# Master.net
KiCad netlist of a schematic drawn in EAGLE
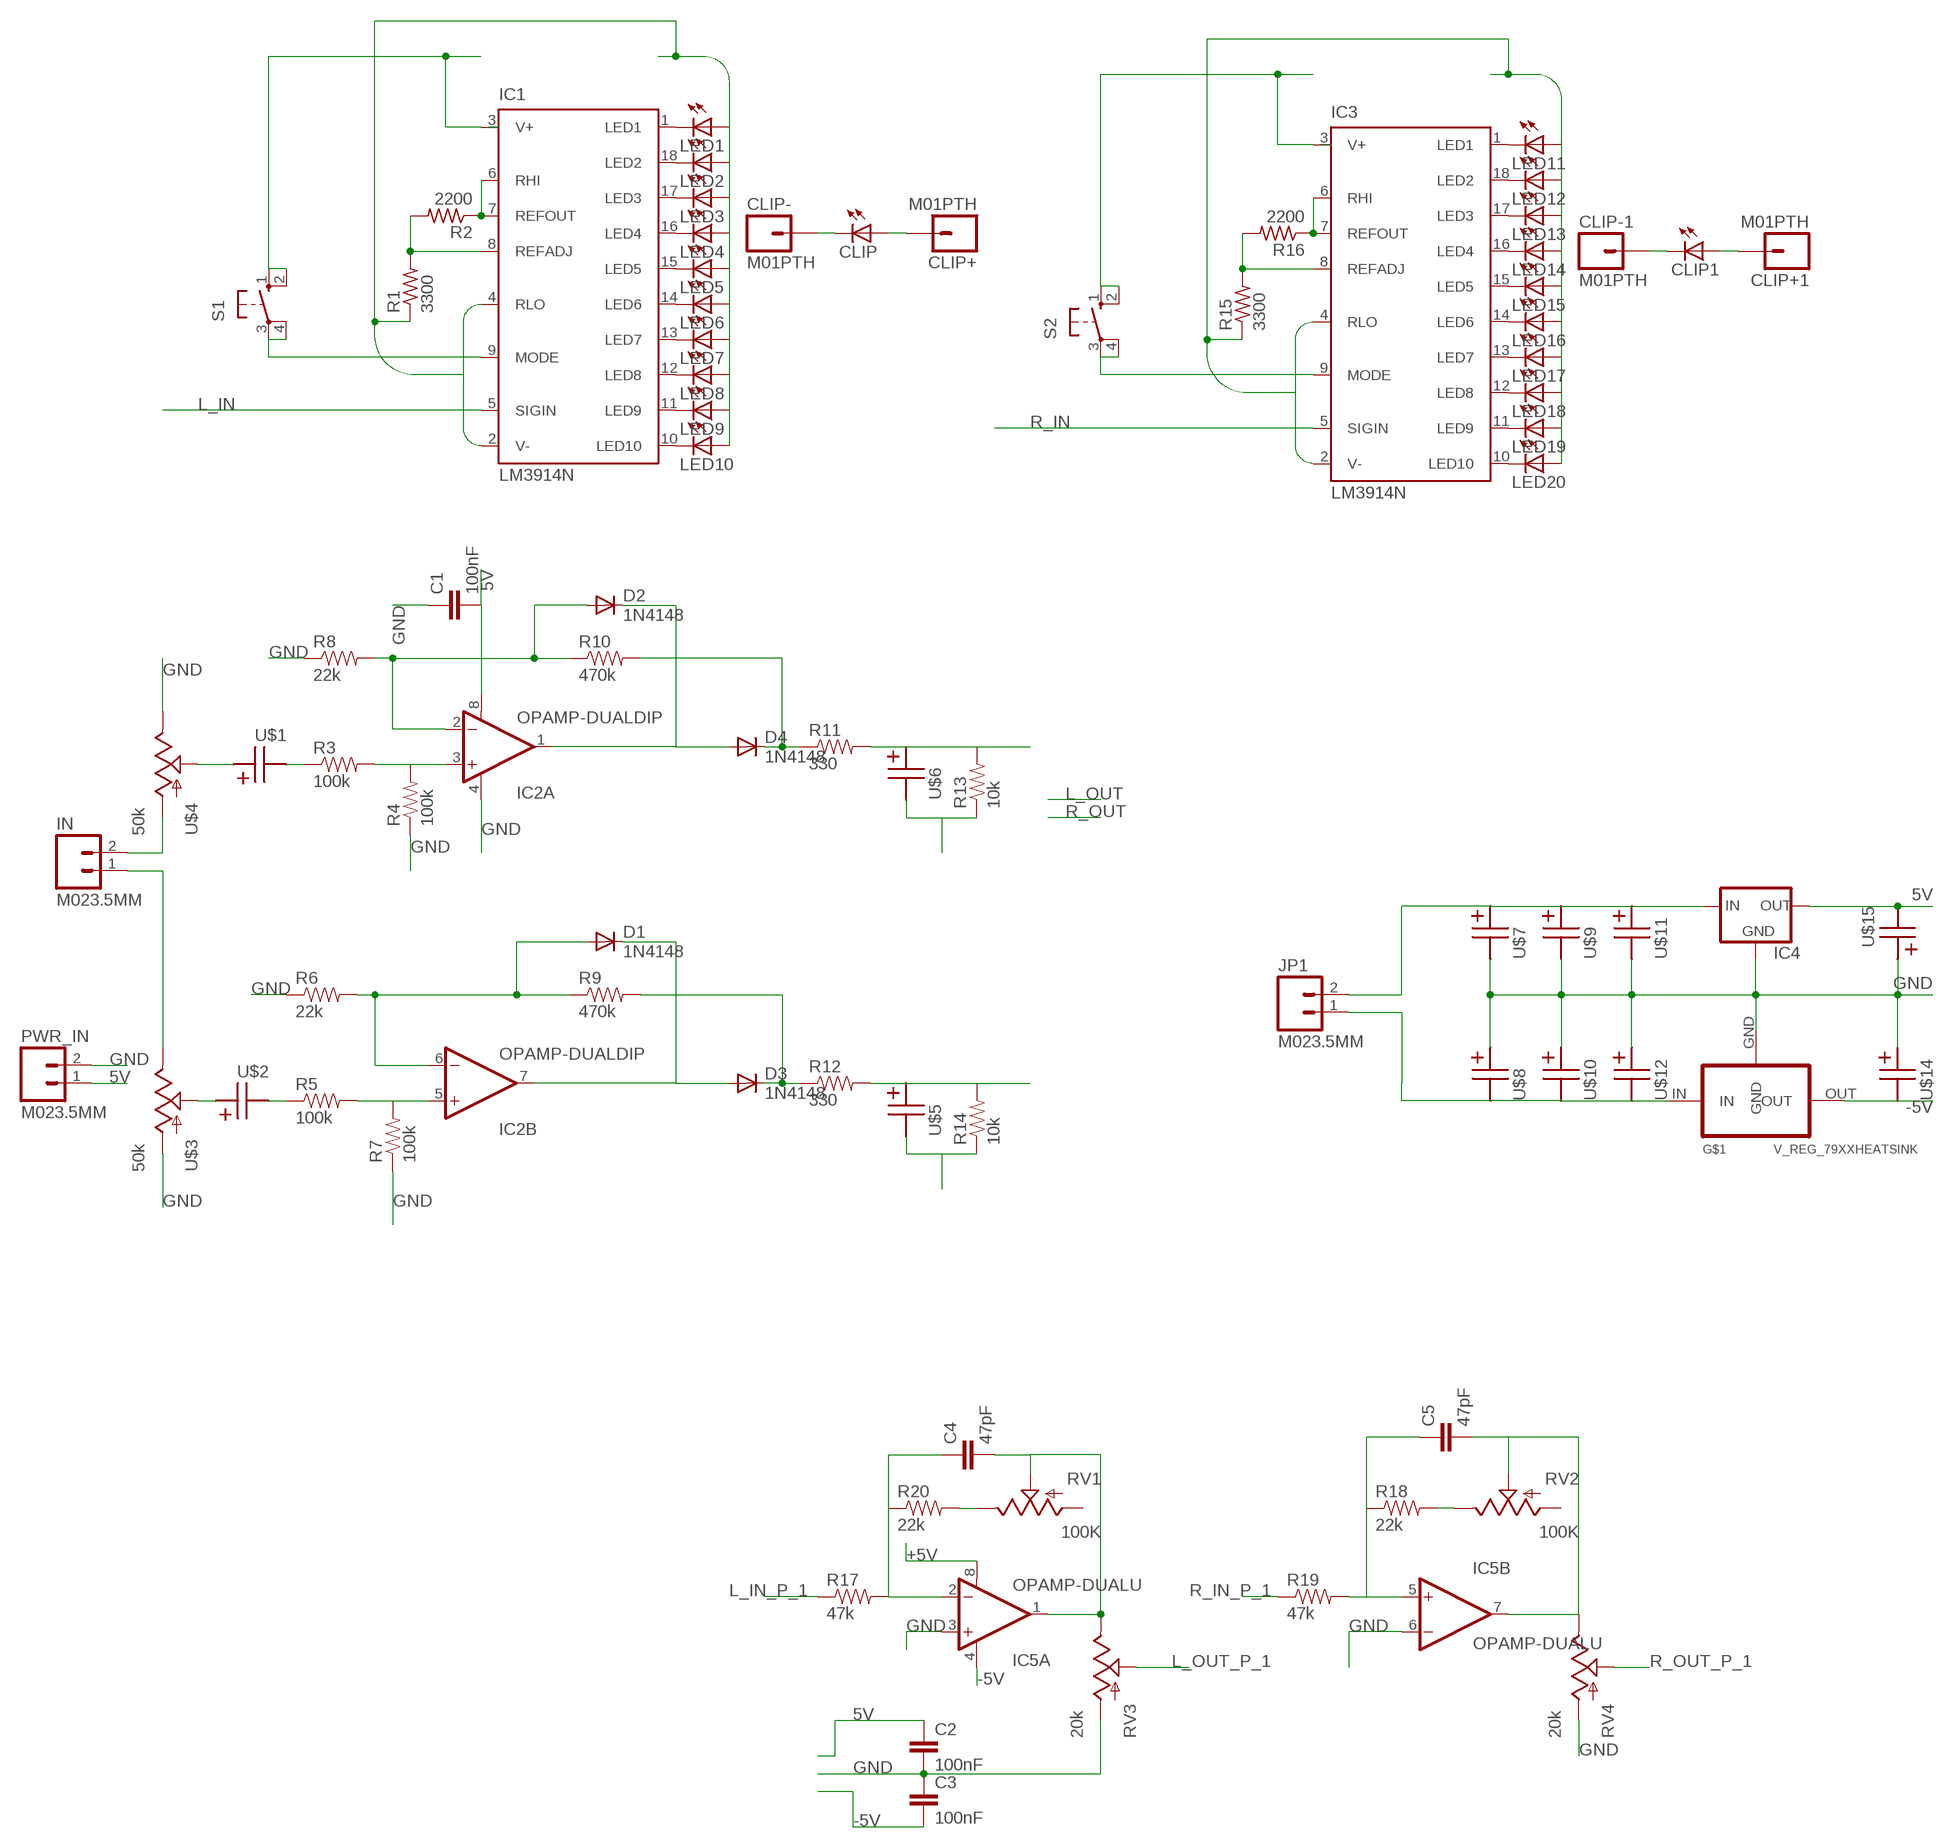
[diagram p0: schematic, sheet 1]

(export (version "E")
  (design (tool "Eeschema 10.0.6"))
  (components
    (comp (ref "C1")
      (value "100nF")
      (footprint "eagle-import:0805")
      (libsource (lib "eagle-import") (part "CAP0805"))
    )
    (comp (ref "C2")
      (value "100nF")
      (footprint "eagle-import:1206")
      (libsource (lib "eagle-import") (part "CAP1206"))
    )
    (comp (ref "C3")
      (value "100nF")
      (footprint "eagle-import:1206")
      (libsource (lib "eagle-import") (part "CAP1206"))
    )
    (comp (ref "C4")
      (value "47pF")
      (footprint "eagle-import:0805")
      (libsource (lib "eagle-import") (part "CAP0805"))
    )
    (comp (ref "C5")
      (value "47pF")
      (footprint "eagle-import:0805")
      (libsource (lib "eagle-import") (part "CAP0805"))
    )
    (comp (ref "CLIP")
      (value "LED5MM")
      (footprint "eagle-import:LED5MM")
      (libsource (lib "eagle-import") (part "LED5MM"))
    )
    (comp (ref "CLIP+")
      (value "M01PTH")
      (footprint "eagle-import:1X01")
      (libsource (lib "eagle-import") (part "M01PTH"))
    )
    (comp (ref "CLIP+1")
      (value "M01PTH")
      (footprint "eagle-import:1X01")
      (libsource (lib "eagle-import") (part "M01PTH"))
    )
    (comp (ref "CLIP-")
      (value "M01PTH")
      (footprint "eagle-import:1X01")
      (libsource (lib "eagle-import") (part "M01PTH"))
    )
    (comp (ref "CLIP-1")
      (value "M01PTH")
      (footprint "eagle-import:1X01")
      (libsource (lib "eagle-import") (part "M01PTH"))
    )
    (comp (ref "CLIP1")
      (value "LED5MM")
      (footprint "eagle-import:LED5MM")
      (libsource (lib "eagle-import") (part "LED5MM"))
    )
    (comp (ref "D1")
      (value "1N4148")
      (footprint "eagle-import:DIODE-1N4148")
      (libsource (lib "eagle-import") (part "DIODE1N4148"))
    )
    (comp (ref "D2")
      (value "1N4148")
      (footprint "eagle-import:DIODE-1N4148")
      (libsource (lib "eagle-import") (part "DIODE1N4148"))
    )
    (comp (ref "D3")
      (value "1N4148")
      (footprint "eagle-import:DIODE-1N4148")
      (libsource (lib "eagle-import") (part "DIODE1N4148"))
    )
    (comp (ref "D4")
      (value "1N4148")
      (footprint "eagle-import:DIODE-1N4148")
      (libsource (lib "eagle-import") (part "DIODE1N4148"))
    )
    (comp (ref "IC1")
      (value "LM3914N")
      (footprint "eagle-import:DIL18")
      (libsource (lib "eagle-import") (part "LM391N4"))
    )
    (comp (ref "IC2")
      (value "OPAMP-DUALDIP")
      (footprint "eagle-import:DIP08")
      (libsource (lib "eagle-import") (part "OPAMP-DUALDIP"))
    )
    (comp (ref "IC3")
      (value "LM3914N")
      (footprint "eagle-import:DIL18")
      (libsource (lib "eagle-import") (part "LM391N4"))
    )
    (comp (ref "IC4")
      (value "V_REG_78XXSINK")
      (footprint "eagle-import:TO220-IGO")
      (libsource (lib "eagle-import") (part "V_REG_78XXSINK"))
    )
    (comp (ref "IC5")
      (value "OPAMP-DUALU")
      (footprint "eagle-import:SO08")
      (libsource (lib "eagle-import") (part "OPAMP-DUALU"))
    )
    (comp (ref "IN")
      (value "M023.5MM")
      (footprint "eagle-import:SCREWTERMINAL-3.5MM-2")
      (libsource (lib "eagle-import") (part "M023.5MM"))
    )
    (comp (ref "JP1")
      (value "M023.5MM")
      (footprint "eagle-import:SCREWTERMINAL-3.5MM-2")
      (libsource (lib "eagle-import") (part "M023.5MM"))
    )
    (comp (ref "LED1")
      (value "LED5MM")
      (footprint "eagle-import:LED5MM")
      (libsource (lib "eagle-import") (part "LED5MM"))
    )
    (comp (ref "LED2")
      (value "LED5MM")
      (footprint "eagle-import:LED5MM")
      (libsource (lib "eagle-import") (part "LED5MM"))
    )
    (comp (ref "LED3")
      (value "LED5MM")
      (footprint "eagle-import:LED5MM")
      (libsource (lib "eagle-import") (part "LED5MM"))
    )
    (comp (ref "LED4")
      (value "LED5MM")
      (footprint "eagle-import:LED5MM")
      (libsource (lib "eagle-import") (part "LED5MM"))
    )
    (comp (ref "LED5")
      (value "LED5MM")
      (footprint "eagle-import:LED5MM")
      (libsource (lib "eagle-import") (part "LED5MM"))
    )
    (comp (ref "LED6")
      (value "LED5MM")
      (footprint "eagle-import:LED5MM")
      (libsource (lib "eagle-import") (part "LED5MM"))
    )
    (comp (ref "LED7")
      (value "LED5MM")
      (footprint "eagle-import:LED5MM")
      (libsource (lib "eagle-import") (part "LED5MM"))
    )
    (comp (ref "LED8")
      (value "LED5MM")
      (footprint "eagle-import:LED5MM")
      (libsource (lib "eagle-import") (part "LED5MM"))
    )
    (comp (ref "LED9")
      (value "LED5MM")
      (footprint "eagle-import:LED5MM")
      (libsource (lib "eagle-import") (part "LED5MM"))
    )
    (comp (ref "LED10")
      (value "LED5MM")
      (footprint "eagle-import:LED5MM")
      (libsource (lib "eagle-import") (part "LED5MM"))
    )
    (comp (ref "LED11")
      (value "LED5MM")
      (footprint "eagle-import:LED5MM")
      (libsource (lib "eagle-import") (part "LED5MM"))
    )
    (comp (ref "LED12")
      (value "LED5MM")
      (footprint "eagle-import:LED5MM")
      (libsource (lib "eagle-import") (part "LED5MM"))
    )
    (comp (ref "LED13")
      (value "LED5MM")
      (footprint "eagle-import:LED5MM")
      (libsource (lib "eagle-import") (part "LED5MM"))
    )
    (comp (ref "LED14")
      (value "LED5MM")
      (footprint "eagle-import:LED5MM")
      (libsource (lib "eagle-import") (part "LED5MM"))
    )
    (comp (ref "LED15")
      (value "LED5MM")
      (footprint "eagle-import:LED5MM")
      (libsource (lib "eagle-import") (part "LED5MM"))
    )
    (comp (ref "LED16")
      (value "LED5MM")
      (footprint "eagle-import:LED5MM")
      (libsource (lib "eagle-import") (part "LED5MM"))
    )
    (comp (ref "LED17")
      (value "LED5MM")
      (footprint "eagle-import:LED5MM")
      (libsource (lib "eagle-import") (part "LED5MM"))
    )
    (comp (ref "LED18")
      (value "LED5MM")
      (footprint "eagle-import:LED5MM")
      (libsource (lib "eagle-import") (part "LED5MM"))
    )
    (comp (ref "LED19")
      (value "LED5MM")
      (footprint "eagle-import:LED5MM")
      (libsource (lib "eagle-import") (part "LED5MM"))
    )
    (comp (ref "LED20")
      (value "LED5MM")
      (footprint "eagle-import:LED5MM")
      (libsource (lib "eagle-import") (part "LED5MM"))
    )
    (comp (ref "PWR_IN")
      (value "M023.5MM")
      (footprint "eagle-import:SCREWTERMINAL-3.5MM-2")
      (libsource (lib "eagle-import") (part "M023.5MM"))
    )
    (comp (ref "R1")
      (value "3300")
      (footprint "eagle-import:0204_5")
      (libsource (lib "eagle-import") (part "R-US_0204/5"))
    )
    (comp (ref "R2")
      (value "2200")
      (footprint "eagle-import:0204_5")
      (libsource (lib "eagle-import") (part "R-US_0204/5"))
    )
    (comp (ref "R3")
      (value "100k")
      (footprint "eagle-import:AXIAL-0.4")
      (libsource (lib "eagle-import") (part "SparkFun-Resistors_RESISTORPTH-1/4W"))
    )
    (comp (ref "R4")
      (value "100k")
      (footprint "eagle-import:AXIAL-0.4")
      (libsource (lib "eagle-import") (part "SparkFun-Resistors_RESISTORPTH-1/4W"))
    )
    (comp (ref "R5")
      (value "100k")
      (footprint "eagle-import:AXIAL-0.4")
      (libsource (lib "eagle-import") (part "SparkFun-Resistors_RESISTORPTH-1/4W"))
    )
    (comp (ref "R6")
      (value "22k")
      (footprint "eagle-import:AXIAL-0.4")
      (libsource (lib "eagle-import") (part "SparkFun-Resistors_RESISTORPTH-1/4W"))
    )
    (comp (ref "R7")
      (value "100k")
      (footprint "eagle-import:AXIAL-0.4")
      (libsource (lib "eagle-import") (part "SparkFun-Resistors_RESISTORPTH-1/4W"))
    )
    (comp (ref "R8")
      (value "22k")
      (footprint "eagle-import:AXIAL-0.4")
      (libsource (lib "eagle-import") (part "SparkFun-Resistors_RESISTORPTH-1/4W"))
    )
    (comp (ref "R9")
      (value "470k")
      (footprint "eagle-import:AXIAL-0.4")
      (libsource (lib "eagle-import") (part "SparkFun-Resistors_RESISTORPTH-1/4W"))
    )
    (comp (ref "R10")
      (value "470k")
      (footprint "eagle-import:AXIAL-0.4")
      (libsource (lib "eagle-import") (part "SparkFun-Resistors_RESISTORPTH-1/4W"))
    )
    (comp (ref "R11")
      (value "330")
      (footprint "eagle-import:AXIAL-0.4")
      (libsource (lib "eagle-import") (part "SparkFun-Resistors_RESISTORPTH-1/4W"))
    )
    (comp (ref "R12")
      (value "330")
      (footprint "eagle-import:AXIAL-0.4")
      (libsource (lib "eagle-import") (part "SparkFun-Resistors_RESISTORPTH-1/4W"))
    )
    (comp (ref "R13")
      (value "10k")
      (footprint "eagle-import:AXIAL-0.4")
      (libsource (lib "eagle-import") (part "SparkFun-Resistors_RESISTORPTH-1/4W"))
    )
    (comp (ref "R14")
      (value "10k")
      (footprint "eagle-import:AXIAL-0.4")
      (libsource (lib "eagle-import") (part "SparkFun-Resistors_RESISTORPTH-1/4W"))
    )
    (comp (ref "R15")
      (value "3300")
      (footprint "eagle-import:0204_5")
      (libsource (lib "eagle-import") (part "R-US_0204/5"))
    )
    (comp (ref "R16")
      (value "2200")
      (footprint "eagle-import:0204_5")
      (libsource (lib "eagle-import") (part "R-US_0204/5"))
    )
    (comp (ref "R17")
      (value "47k")
      (footprint "eagle-import:AXIAL-0.4")
      (libsource (lib "eagle-import") (part "RESISTORPTH-1/4W"))
    )
    (comp (ref "R18")
      (value "22k")
      (footprint "eagle-import:AXIAL-0.4")
      (libsource (lib "eagle-import") (part "RESISTORPTH-1/4W"))
    )
    (comp (ref "R19")
      (value "47k")
      (footprint "eagle-import:AXIAL-0.4")
      (libsource (lib "eagle-import") (part "RESISTORPTH-1/4W"))
    )
    (comp (ref "R20")
      (value "22k")
      (footprint "eagle-import:AXIAL-0.4")
      (libsource (lib "eagle-import") (part "RESISTORPTH-1/4W"))
    )
    (comp (ref "RV1")
      (value "100K")
      (footprint "eagle-import:TRIM_POT")
      (libsource (lib "eagle-import") (part "POTTRIM"))
    )
    (comp (ref "RV2")
      (value "100K")
      (footprint "eagle-import:TRIM_POT")
      (libsource (lib "eagle-import") (part "POTTRIM"))
    )
    (comp (ref "RV3")
      (value "20k")
      (footprint "eagle-import:ALPS_POT")
      (libsource (lib "eagle-import") (part "POT"))
    )
    (comp (ref "RV4")
      (value "20k")
      (footprint "eagle-import:ALPS_POT")
      (libsource (lib "eagle-import") (part "POT"))
    )
    (comp (ref "S1")
      (value "10-XX")
      (footprint "eagle-import:B3F-10XX")
      (fields (field (name "MPN") "B3F-1000"))
      (libsource (lib "eagle-import") (part "10-XX"))
    )
    (comp (ref "S2")
      (value "10-XX")
      (footprint "eagle-import:B3F-10XX")
      (fields (field (name "MPN") "B3F-1000"))
      (libsource (lib "eagle-import") (part "10-XX"))
    )
    (comp (ref "U$1")
      (value "6.8uF")
      (footprint "eagle-import:2MMLEAD_5MMDIAMETER")
      (libsource (lib "eagle-import") (part "5MM-12.5MM-POLAR2MMX5MM"))
    )
    (comp (ref "U$2")
      (value "6.8uF")
      (footprint "eagle-import:2MMLEAD_5MMDIAMETER")
      (libsource (lib "eagle-import") (part "5MM-12.5MM-POLAR2MMX5MM"))
    )
    (comp (ref "U$3")
      (value "50k")
      (footprint "eagle-import:ALPS_POT")
      (libsource (lib "eagle-import") (part "POT"))
    )
    (comp (ref "U$4")
      (value "50k")
      (footprint "eagle-import:ALPS_POT")
      (libsource (lib "eagle-import") (part "POT"))
    )
    (comp (ref "U$5")
      (value "2.2uF")
      (footprint "eagle-import:2MMLEAD_5MMDIAMETER")
      (libsource (lib "eagle-import") (part "5MM-12.5MM-POLAR2MMX5MM"))
    )
    (comp (ref "U$6")
      (value "2.2uF")
      (footprint "eagle-import:2MMLEAD_5MMDIAMETER")
      (libsource (lib "eagle-import") (part "5MM-12.5MM-POLAR2MMX5MM"))
    )
    (comp (ref "U$7")
      (value "5MM-12.5MM-POLAR5MMX12.5MM")
      (footprint "eagle-import:5MMLEAD_12.5MMDIAMETER")
      (libsource (lib "eagle-import") (part "5MM-12.5MM-POLAR5MMX12.5MM"))
    )
    (comp (ref "U$8")
      (value "5MM-12.5MM-POLAR5MMX12.5MM")
      (footprint "eagle-import:5MMLEAD_12.5MMDIAMETER")
      (libsource (lib "eagle-import") (part "5MM-12.5MM-POLAR5MMX12.5MM"))
    )
    (comp (ref "U$9")
      (value "5MM-12.5MM-POLAR5MMX12.5MM")
      (footprint "eagle-import:5MMLEAD_12.5MMDIAMETER")
      (libsource (lib "eagle-import") (part "5MM-12.5MM-POLAR5MMX12.5MM"))
    )
    (comp (ref "U$10")
      (value "5MM-12.5MM-POLAR5MMX12.5MM")
      (footprint "eagle-import:5MMLEAD_12.5MMDIAMETER")
      (libsource (lib "eagle-import") (part "5MM-12.5MM-POLAR5MMX12.5MM"))
    )
    (comp (ref "U$11")
      (value "5MM-12.5MM-POLAR5MMX12.5MM")
      (footprint "eagle-import:5MMLEAD_12.5MMDIAMETER")
      (libsource (lib "eagle-import") (part "5MM-12.5MM-POLAR5MMX12.5MM"))
    )
    (comp (ref "U$12")
      (value "5MM-12.5MM-POLAR5MMX12.5MM")
      (footprint "eagle-import:5MMLEAD_12.5MMDIAMETER")
      (libsource (lib "eagle-import") (part "5MM-12.5MM-POLAR5MMX12.5MM"))
    )
    (comp (ref "U$13")
      (value "V_REG_79XXHEATSINK")
      (footprint "eagle-import:TO220-IGO")
      (libsource (lib "eagle-import") (part "V_REG_79XXHEATSINK"))
    )
    (comp (ref "U$14")
      (value "5MM-12.5MM-POLAR2MMX5MM")
      (footprint "eagle-import:2MMLEAD_5MMDIAMETER")
      (libsource (lib "eagle-import") (part "5MM-12.5MM-POLAR2MMX5MM"))
    )
    (comp (ref "U$15")
      (value "5MM-12.5MM-POLAR2MMX5MM")
      (footprint "eagle-import:2MMLEAD_5MMDIAMETER")
      (libsource (lib "eagle-import") (part "5MM-12.5MM-POLAR2MMX5MM"))
    )
  )
  (nets
    (net (code "1") (name "/+5V") (class "Default")
      (node (ref "IC5") (pin "8") (pinfunction "V+_8") (pintype "power_in"))
    )
    (net (code "2") (name "/-5V") (class "Default")
      (node (ref "C3") (pin "2") (pinfunction "2_2") (pintype "passive"))
      (node (ref "IC5") (pin "4") (pinfunction "V-_4") (pintype "power_in"))
      (node (ref "U$13") (pin "OUT") (pinfunction "OUT_OUT") (pintype "bidirectional"))
      (node (ref "U$14") (pin "+") (pinfunction "-_+") (pintype "bidirectional"))
    )
    (net (code "3") (name "/5V") (class "Default")
      (node (ref "C1") (pin "2") (pinfunction "2_2") (pintype "passive"))
      (node (ref "C2") (pin "1") (pinfunction "1_1") (pintype "passive"))
      (node (ref "IC1") (pin "3") (pinfunction "V+_3") (pintype "power_in"))
      (node (ref "IC2") (pin "8") (pinfunction "V+_8") (pintype "power_in"))
      (node (ref "IC3") (pin "3") (pinfunction "V+_3") (pintype "power_in"))
      (node (ref "IC4") (pin "OUT") (pinfunction "OUT_OUT") (pintype "output"))
      (node (ref "PWR_IN") (pin "1") (pinfunction "1_1") (pintype "passive"))
      (node (ref "S1") (pin "1") (pinfunction "S_1") (pintype "passive"))
      (node (ref "S1") (pin "2") (pinfunction "S1_2") (pintype "passive"))
      (node (ref "S2") (pin "1") (pinfunction "S_1") (pintype "passive"))
      (node (ref "S2") (pin "2") (pinfunction "S1_2") (pintype "passive"))
      (node (ref "U$15") (pin "+") (pinfunction "-_+") (pintype "bidirectional"))
    )
    (net (code "4") (name "/GND") (class "Default")
      (node (ref "C1") (pin "1") (pinfunction "1_1") (pintype "passive"))
      (node (ref "C2") (pin "2") (pinfunction "2_2") (pintype "passive"))
      (node (ref "C3") (pin "1") (pinfunction "1_1") (pintype "passive"))
      (node (ref "IC1") (pin "2") (pinfunction "V-_2") (pintype "power_in"))
      (node (ref "IC1") (pin "4") (pinfunction "RLO_4") (pintype "input"))
      (node (ref "IC2") (pin "4") (pinfunction "V-_4") (pintype "power_in"))
      (node (ref "IC3") (pin "2") (pinfunction "V-_2") (pintype "power_in"))
      (node (ref "IC3") (pin "4") (pinfunction "RLO_4") (pintype "input"))
      (node (ref "IC4") (pin "GND") (pinfunction "GND_GND") (pintype "input"))
      (node (ref "IC5") (pin "3") (pinfunction "+IN_3") (pintype "input"))
      (node (ref "IC5") (pin "6") (pinfunction "-IN_6") (pintype "input"))
      (node (ref "LED1") (pin "A") (pinfunction "A_A") (pintype "passive"))
      (node (ref "LED10") (pin "A") (pinfunction "A_A") (pintype "passive"))
      (node (ref "LED11") (pin "A") (pinfunction "A_A") (pintype "passive"))
      (node (ref "LED12") (pin "A") (pinfunction "A_A") (pintype "passive"))
      (node (ref "LED13") (pin "A") (pinfunction "A_A") (pintype "passive"))
      (node (ref "LED14") (pin "A") (pinfunction "A_A") (pintype "passive"))
      (node (ref "LED15") (pin "A") (pinfunction "A_A") (pintype "passive"))
      (node (ref "LED16") (pin "A") (pinfunction "A_A") (pintype "passive"))
      (node (ref "LED17") (pin "A") (pinfunction "A_A") (pintype "passive"))
      (node (ref "LED18") (pin "A") (pinfunction "A_A") (pintype "passive"))
      (node (ref "LED19") (pin "A") (pinfunction "A_A") (pintype "passive"))
      (node (ref "LED2") (pin "A") (pinfunction "A_A") (pintype "passive"))
      (node (ref "LED20") (pin "A") (pinfunction "A_A") (pintype "passive"))
      (node (ref "LED3") (pin "A") (pinfunction "A_A") (pintype "passive"))
      (node (ref "LED4") (pin "A") (pinfunction "A_A") (pintype "passive"))
      (node (ref "LED5") (pin "A") (pinfunction "A_A") (pintype "passive"))
      (node (ref "LED6") (pin "A") (pinfunction "A_A") (pintype "passive"))
      (node (ref "LED7") (pin "A") (pinfunction "A_A") (pintype "passive"))
      (node (ref "LED8") (pin "A") (pinfunction "A_A") (pintype "passive"))
      (node (ref "LED9") (pin "A") (pinfunction "A_A") (pintype "passive"))
      (node (ref "PWR_IN") (pin "2") (pinfunction "2_2") (pintype "passive"))
      (node (ref "R1") (pin "1") (pinfunction "1_1") (pintype "passive"))
      (node (ref "R13") (pin "P$1") (pinfunction "1_P$1") (pintype "passive"))
      (node (ref "R14") (pin "P$1") (pinfunction "1_P$1") (pintype "passive"))
      (node (ref "R15") (pin "1") (pinfunction "1_1") (pintype "passive"))
      (node (ref "R4") (pin "P$1") (pinfunction "1_P$1") (pintype "passive"))
      (node (ref "R6") (pin "P$1") (pinfunction "1_P$1") (pintype "passive"))
      (node (ref "R7") (pin "P$1") (pinfunction "1_P$1") (pintype "passive"))
      (node (ref "R8") (pin "P$1") (pinfunction "1_P$1") (pintype "passive"))
      (node (ref "RV3") (pin "P$3") (pinfunction "A_P$3") (pintype "passive"))
      (node (ref "RV4") (pin "P$3") (pinfunction "A_P$3") (pintype "passive"))
      (node (ref "U$10") (pin "-") (pinfunction "+_-") (pintype "bidirectional"))
      (node (ref "U$11") (pin "+") (pinfunction "-_+") (pintype "bidirectional"))
      (node (ref "U$12") (pin "-") (pinfunction "+_-") (pintype "bidirectional"))
      (node (ref "U$13") (pin "GND") (pinfunction "GND_GND") (pintype "bidirectional"))
      (node (ref "U$14") (pin "-") (pinfunction "+_-") (pintype "bidirectional"))
      (node (ref "U$15") (pin "-") (pinfunction "+_-") (pintype "bidirectional"))
      (node (ref "U$3") (pin "P$3") (pinfunction "A_P$3") (pintype "passive"))
      (node (ref "U$4") (pin "P$1") (pinfunction "E_P$1") (pintype "passive"))
      (node (ref "U$5") (pin "+") (pinfunction "-_+") (pintype "bidirectional"))
      (node (ref "U$6") (pin "+") (pinfunction "-_+") (pintype "bidirectional"))
      (node (ref "U$7") (pin "+") (pinfunction "-_+") (pintype "bidirectional"))
      (node (ref "U$8") (pin "-") (pinfunction "+_-") (pintype "bidirectional"))
      (node (ref "U$9") (pin "+") (pinfunction "-_+") (pintype "bidirectional"))
    )
    (net (code "5") (name "/L_IN") (class "Default")
      (node (ref "IC1") (pin "5") (pinfunction "SIGIN_5") (pintype "input"))
      (node (ref "IN") (pin "2") (pinfunction "2_2") (pintype "passive"))
      (node (ref "U$4") (pin "P$3") (pinfunction "A_P$3") (pintype "passive"))
    )
    (net (code "6") (name "/L_IN_P_1") (class "Default")
      (node (ref "R17") (pin "P$1") (pinfunction "1_P$1") (pintype "passive"))
    )
    (net (code "7") (name "/L_OUT") (class "Default")
      (node (ref "R11") (pin "P$2") (pinfunction "2_P$2") (pintype "passive"))
      (node (ref "R13") (pin "P$2") (pinfunction "2_P$2") (pintype "passive"))
      (node (ref "U$6") (pin "-") (pinfunction "+_-") (pintype "bidirectional"))
    )
    (net (code "8") (name "/L_OUT_P_1") (class "Default")
      (node (ref "RV3") (pin "P$2") (pinfunction "S_P$2") (pintype "passive"))
    )
    (net (code "9") (name "/R_IN") (class "Default")
      (node (ref "IC3") (pin "5") (pinfunction "SIGIN_5") (pintype "input"))
      (node (ref "IN") (pin "1") (pinfunction "1_1") (pintype "passive"))
      (node (ref "U$3") (pin "P$1") (pinfunction "E_P$1") (pintype "passive"))
    )
    (net (code "10") (name "/R_IN_P_1") (class "Default")
      (node (ref "R19") (pin "P$1") (pinfunction "1_P$1") (pintype "passive"))
    )
    (net (code "11") (name "/R_OUT") (class "Default")
      (node (ref "R12") (pin "P$2") (pinfunction "2_P$2") (pintype "passive"))
      (node (ref "R14") (pin "P$2") (pinfunction "2_P$2") (pintype "passive"))
      (node (ref "U$5") (pin "-") (pinfunction "+_-") (pintype "bidirectional"))
    )
    (net (code "12") (name "/R_OUT_P_1") (class "Default")
      (node (ref "RV4") (pin "P$2") (pinfunction "S_P$2") (pintype "passive"))
    )
    (net (code "13") (name "Net-(CLIP+-Pad1)") (class "Default")
      (node (ref "CLIP") (pin "A") (pinfunction "A_A") (pintype "passive"))
      (node (ref "CLIP+") (pin "1") (pinfunction "1_1") (pintype "passive"))
    )
    (net (code "14") (name "Net-(CLIP+1-Pad1)") (class "Default")
      (node (ref "CLIP+1") (pin "1") (pinfunction "1_1") (pintype "passive"))
      (node (ref "CLIP1") (pin "A") (pinfunction "A_A") (pintype "passive"))
    )
    (net (code "15") (name "Net-(CLIP-C)") (class "Default")
      (node (ref "CLIP") (pin "K") (pinfunction "C_K") (pintype "passive"))
      (node (ref "CLIP-") (pin "1") (pinfunction "1_1") (pintype "passive"))
    )
    (net (code "16") (name "Net-(CLIP1-C)") (class "Default")
      (node (ref "CLIP-1") (pin "1") (pinfunction "1_1") (pintype "passive"))
      (node (ref "CLIP1") (pin "K") (pinfunction "C_K") (pintype "passive"))
    )
    (net (code "17") (name "Net-(IC1-LED1)") (class "Default")
      (node (ref "IC1") (pin "1") (pinfunction "LED1_1") (pintype "output"))
      (node (ref "LED1") (pin "K") (pinfunction "C_K") (pintype "passive"))
    )
    (net (code "18") (name "Net-(IC1-LED2)") (class "Default")
      (node (ref "IC1") (pin "18") (pinfunction "LED2_18") (pintype "output"))
      (node (ref "LED2") (pin "K") (pinfunction "C_K") (pintype "passive"))
    )
    (net (code "19") (name "Net-(IC1-LED3)") (class "Default")
      (node (ref "IC1") (pin "17") (pinfunction "LED3_17") (pintype "output"))
      (node (ref "LED3") (pin "K") (pinfunction "C_K") (pintype "passive"))
    )
    (net (code "20") (name "Net-(IC1-LED4)") (class "Default")
      (node (ref "IC1") (pin "16") (pinfunction "LED4_16") (pintype "output"))
      (node (ref "LED4") (pin "K") (pinfunction "C_K") (pintype "passive"))
    )
    (net (code "21") (name "Net-(IC1-LED5)") (class "Default")
      (node (ref "IC1") (pin "15") (pinfunction "LED5_15") (pintype "output"))
      (node (ref "LED5") (pin "K") (pinfunction "C_K") (pintype "passive"))
    )
    (net (code "22") (name "Net-(IC1-LED6)") (class "Default")
      (node (ref "IC1") (pin "14") (pinfunction "LED6_14") (pintype "output"))
      (node (ref "LED6") (pin "K") (pinfunction "C_K") (pintype "passive"))
    )
    (net (code "23") (name "Net-(IC1-LED7)") (class "Default")
      (node (ref "IC1") (pin "13") (pinfunction "LED7_13") (pintype "output"))
      (node (ref "LED7") (pin "K") (pinfunction "C_K") (pintype "passive"))
    )
    (net (code "24") (name "Net-(IC1-LED8)") (class "Default")
      (node (ref "IC1") (pin "12") (pinfunction "LED8_12") (pintype "output"))
      (node (ref "LED8") (pin "K") (pinfunction "C_K") (pintype "passive"))
    )
    (net (code "25") (name "Net-(IC1-LED9)") (class "Default")
      (node (ref "IC1") (pin "11") (pinfunction "LED9_11") (pintype "output"))
      (node (ref "LED9") (pin "K") (pinfunction "C_K") (pintype "passive"))
    )
    (net (code "26") (name "Net-(IC1-LED10)") (class "Default")
      (node (ref "IC1") (pin "10") (pinfunction "LED10_10") (pintype "output"))
      (node (ref "LED10") (pin "K") (pinfunction "C_K") (pintype "passive"))
    )
    (net (code "27") (name "Net-(IC1-MODE)") (class "Default")
      (node (ref "IC1") (pin "9") (pinfunction "MODE_9") (pintype "input"))
      (node (ref "S1") (pin "3") (pinfunction "P_3") (pintype "passive"))
      (node (ref "S1") (pin "4") (pinfunction "P1_4") (pintype "passive"))
    )
    (net (code "28") (name "Net-(IC1-REFADJ)") (class "Default")
      (node (ref "IC1") (pin "8") (pinfunction "REFADJ_8") (pintype "passive"))
      (node (ref "R1") (pin "2") (pinfunction "2_2") (pintype "passive"))
      (node (ref "R2") (pin "2") (pinfunction "2_2") (pintype "passive"))
    )
    (net (code "29") (name "Net-(IC1-REFOUT)") (class "Default")
      (node (ref "IC1") (pin "6") (pinfunction "RHI_6") (pintype "input"))
      (node (ref "IC1") (pin "7") (pinfunction "REFOUT_7") (pintype "output"))
      (node (ref "R2") (pin "1") (pinfunction "1_1") (pintype "passive"))
    )
    (net (code "30") (name "Net-(IC2A-+IN)") (class "Default")
      (node (ref "IC2") (pin "3") (pinfunction "+IN_3") (pintype "input"))
      (node (ref "R3") (pin "P$2") (pinfunction "2_P$2") (pintype "passive"))
      (node (ref "R4") (pin "P$2") (pinfunction "2_P$2") (pintype "passive"))
    )
    (net (code "31") (name "Net-(IC2A--IN)") (class "Default")
      (node (ref "D2") (pin "A") (pinfunction "A_A") (pintype "passive"))
      (node (ref "IC2") (pin "2") (pinfunction "-IN_2") (pintype "input"))
      (node (ref "R10") (pin "P$1") (pinfunction "1_P$1") (pintype "passive"))
      (node (ref "R8") (pin "P$2") (pinfunction "2_P$2") (pintype "passive"))
    )
    (net (code "32") (name "Net-(IC2A-OUT)") (class "Default")
      (node (ref "D2") (pin "C") (pinfunction "C_C") (pintype "passive"))
      (node (ref "D4") (pin "A") (pinfunction "A_A") (pintype "passive"))
      (node (ref "IC2") (pin "1") (pinfunction "OUT_1") (pintype "output"))
    )
    (net (code "33") (name "Net-(IC2B-+IN)") (class "Default")
      (node (ref "IC2") (pin "5") (pinfunction "+IN_5") (pintype "input"))
      (node (ref "R5") (pin "P$2") (pinfunction "2_P$2") (pintype "passive"))
      (node (ref "R7") (pin "P$2") (pinfunction "2_P$2") (pintype "passive"))
    )
    (net (code "34") (name "Net-(IC2B--IN)") (class "Default")
      (node (ref "D1") (pin "A") (pinfunction "A_A") (pintype "passive"))
      (node (ref "IC2") (pin "6") (pinfunction "-IN_6") (pintype "input"))
      (node (ref "R6") (pin "P$2") (pinfunction "2_P$2") (pintype "passive"))
      (node (ref "R9") (pin "P$1") (pinfunction "1_P$1") (pintype "passive"))
    )
    (net (code "35") (name "Net-(IC2B-OUT)") (class "Default")
      (node (ref "D1") (pin "C") (pinfunction "C_C") (pintype "passive"))
      (node (ref "D3") (pin "A") (pinfunction "A_A") (pintype "passive"))
      (node (ref "IC2") (pin "7") (pinfunction "OUT_7") (pintype "output"))
    )
    (net (code "36") (name "Net-(IC3-LED1)") (class "Default")
      (node (ref "IC3") (pin "1") (pinfunction "LED1_1") (pintype "output"))
      (node (ref "LED11") (pin "K") (pinfunction "C_K") (pintype "passive"))
    )
    (net (code "37") (name "Net-(IC3-LED2)") (class "Default")
      (node (ref "IC3") (pin "18") (pinfunction "LED2_18") (pintype "output"))
      (node (ref "LED12") (pin "K") (pinfunction "C_K") (pintype "passive"))
    )
    (net (code "38") (name "Net-(IC3-LED3)") (class "Default")
      (node (ref "IC3") (pin "17") (pinfunction "LED3_17") (pintype "output"))
      (node (ref "LED13") (pin "K") (pinfunction "C_K") (pintype "passive"))
    )
    (net (code "39") (name "Net-(IC3-LED4)") (class "Default")
      (node (ref "IC3") (pin "16") (pinfunction "LED4_16") (pintype "output"))
      (node (ref "LED14") (pin "K") (pinfunction "C_K") (pintype "passive"))
    )
    (net (code "40") (name "Net-(IC3-LED5)") (class "Default")
      (node (ref "IC3") (pin "15") (pinfunction "LED5_15") (pintype "output"))
      (node (ref "LED15") (pin "K") (pinfunction "C_K") (pintype "passive"))
    )
    (net (code "41") (name "Net-(IC3-LED6)") (class "Default")
      (node (ref "IC3") (pin "14") (pinfunction "LED6_14") (pintype "output"))
      (node (ref "LED16") (pin "K") (pinfunction "C_K") (pintype "passive"))
    )
    (net (code "42") (name "Net-(IC3-LED7)") (class "Default")
      (node (ref "IC3") (pin "13") (pinfunction "LED7_13") (pintype "output"))
      (node (ref "LED17") (pin "K") (pinfunction "C_K") (pintype "passive"))
    )
    (net (code "43") (name "Net-(IC3-LED8)") (class "Default")
      (node (ref "IC3") (pin "12") (pinfunction "LED8_12") (pintype "output"))
      (node (ref "LED18") (pin "K") (pinfunction "C_K") (pintype "passive"))
    )
    (net (code "44") (name "Net-(IC3-LED9)") (class "Default")
      (node (ref "IC3") (pin "11") (pinfunction "LED9_11") (pintype "output"))
      (node (ref "LED19") (pin "K") (pinfunction "C_K") (pintype "passive"))
    )
    (net (code "45") (name "Net-(IC3-LED10)") (class "Default")
      (node (ref "IC3") (pin "10") (pinfunction "LED10_10") (pintype "output"))
      (node (ref "LED20") (pin "K") (pinfunction "C_K") (pintype "passive"))
    )
    (net (code "46") (name "Net-(IC3-MODE)") (class "Default")
      (node (ref "IC3") (pin "9") (pinfunction "MODE_9") (pintype "input"))
      (node (ref "S2") (pin "3") (pinfunction "P_3") (pintype "passive"))
      (node (ref "S2") (pin "4") (pinfunction "P1_4") (pintype "passive"))
    )
    (net (code "47") (name "Net-(IC3-REFADJ)") (class "Default")
      (node (ref "IC3") (pin "8") (pinfunction "REFADJ_8") (pintype "passive"))
      (node (ref "R15") (pin "2") (pinfunction "2_2") (pintype "passive"))
      (node (ref "R16") (pin "2") (pinfunction "2_2") (pintype "passive"))
    )
    (net (code "48") (name "Net-(IC3-REFOUT)") (class "Default")
      (node (ref "IC3") (pin "6") (pinfunction "RHI_6") (pintype "input"))
      (node (ref "IC3") (pin "7") (pinfunction "REFOUT_7") (pintype "output"))
      (node (ref "R16") (pin "1") (pinfunction "1_1") (pintype "passive"))
    )
    (net (code "49") (name "Net-(IC5A--IN)") (class "Default")
      (node (ref "C4") (pin "1") (pinfunction "1_1") (pintype "passive"))
      (node (ref "IC5") (pin "2") (pinfunction "-IN_2") (pintype "input"))
      (node (ref "R17") (pin "P$2") (pinfunction "2_P$2") (pintype "passive"))
      (node (ref "R20") (pin "P$1") (pinfunction "1_P$1") (pintype "passive"))
    )
    (net (code "50") (name "Net-(IC5A-OUT)") (class "Default")
      (node (ref "C4") (pin "2") (pinfunction "2_2") (pintype "passive"))
      (node (ref "IC5") (pin "1") (pinfunction "OUT_1") (pintype "output"))
      (node (ref "RV1") (pin "1") (pinfunction "S_1") (pintype "passive"))
      (node (ref "RV3") (pin "P$1") (pinfunction "E_P$1") (pintype "passive"))
    )
    (net (code "51") (name "Net-(IC5B-+IN)") (class "Default")
      (node (ref "C5") (pin "1") (pinfunction "1_1") (pintype "passive"))
      (node (ref "IC5") (pin "5") (pinfunction "+IN_5") (pintype "input"))
      (node (ref "R18") (pin "P$1") (pinfunction "1_P$1") (pintype "passive"))
      (node (ref "R19") (pin "P$2") (pinfunction "2_P$2") (pintype "passive"))
    )
    (net (code "52") (name "Net-(IC5B-OUT)") (class "Default")
      (node (ref "C5") (pin "2") (pinfunction "2_2") (pintype "passive"))
      (node (ref "IC5") (pin "7") (pinfunction "OUT_7") (pintype "output"))
      (node (ref "RV2") (pin "1") (pinfunction "S_1") (pintype "passive"))
      (node (ref "RV4") (pin "P$1") (pinfunction "E_P$1") (pintype "passive"))
    )
    (net (code "53") (name "Net-(R3-1)") (class "Default")
      (node (ref "R3") (pin "P$1") (pinfunction "1_P$1") (pintype "passive"))
      (node (ref "U$1") (pin "+") (pinfunction "-_+") (pintype "bidirectional"))
    )
    (net (code "54") (name "Net-(R5-1)") (class "Default")
      (node (ref "R5") (pin "P$1") (pinfunction "1_P$1") (pintype "passive"))
      (node (ref "U$2") (pin "+") (pinfunction "-_+") (pintype "bidirectional"))
    )
    (net (code "55") (name "Net-(R10-2)") (class "Default")
      (node (ref "D4") (pin "C") (pinfunction "C_C") (pintype "passive"))
      (node (ref "R10") (pin "P$2") (pinfunction "2_P$2") (pintype "passive"))
      (node (ref "R11") (pin "P$1") (pinfunction "1_P$1") (pintype "passive"))
    )
    (net (code "56") (name "Net-(R12-1)") (class "Default")
      (node (ref "D3") (pin "C") (pinfunction "C_C") (pintype "passive"))
      (node (ref "R12") (pin "P$1") (pinfunction "1_P$1") (pintype "passive"))
      (node (ref "R9") (pin "P$2") (pinfunction "2_P$2") (pintype "passive"))
    )
    (net (code "57") (name "Net-(R18-2)") (class "Default")
      (node (ref "R18") (pin "P$2") (pinfunction "2_P$2") (pintype "passive"))
      (node (ref "RV2") (pin "2") (pinfunction "E_2") (pintype "passive"))
    )
    (net (code "58") (name "Net-(R20-2)") (class "Default")
      (node (ref "R20") (pin "P$2") (pinfunction "2_P$2") (pintype "passive"))
      (node (ref "RV1") (pin "2") (pinfunction "E_2") (pintype "passive"))
    )
    (net (code "59") (name "Net-(U$1-+)") (class "Default")
      (node (ref "U$1") (pin "-") (pinfunction "+_-") (pintype "bidirectional"))
      (node (ref "U$4") (pin "P$2") (pinfunction "S_P$2") (pintype "passive"))
    )
    (net (code "60") (name "Net-(U$2-+)") (class "Default")
      (node (ref "U$2") (pin "-") (pinfunction "+_-") (pintype "bidirectional"))
      (node (ref "U$3") (pin "P$2") (pinfunction "S_P$2") (pintype "passive"))
    )
    (net (code "61") (name "Net-(U$10--)") (class "Default")
      (node (ref "JP1") (pin "1") (pinfunction "1_1") (pintype "passive"))
      (node (ref "U$10") (pin "+") (pinfunction "-_+") (pintype "bidirectional"))
      (node (ref "U$12") (pin "+") (pinfunction "-_+") (pintype "bidirectional"))
      (node (ref "U$13") (pin "IN") (pinfunction "IN_IN") (pintype "bidirectional"))
      (node (ref "U$8") (pin "+") (pinfunction "-_+") (pintype "bidirectional"))
    )
    (net (code "62") (name "Net-(U$11-+)") (class "Default")
      (node (ref "IC4") (pin "IN") (pinfunction "IN_IN") (pintype "input"))
      (node (ref "JP1") (pin "2") (pinfunction "2_2") (pintype "passive"))
      (node (ref "U$11") (pin "-") (pinfunction "+_-") (pintype "bidirectional"))
      (node (ref "U$7") (pin "-") (pinfunction "+_-") (pintype "bidirectional"))
      (node (ref "U$9") (pin "-") (pinfunction "+_-") (pintype "bidirectional"))
    )
    (net (code "63") (name "unconnected-(RV1-A-Pad3)") (class "Default")
      (node (ref "RV1") (pin "3") (pinfunction "A_3") (pintype "passive"))
    )
    (net (code "64") (name "unconnected-(RV2-A-Pad3)") (class "Default")
      (node (ref "RV2") (pin "3") (pinfunction "A_3") (pintype "passive"))
    )
  )
)
